# ExenMiniMotorShield.net
KiCad netlist of a schematic drawn in EAGLE
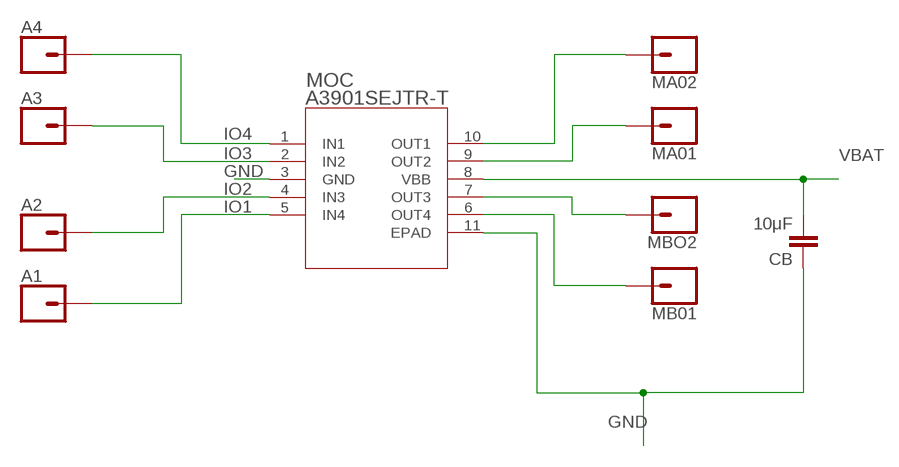
[diagram p0: schematic, sheet 1]
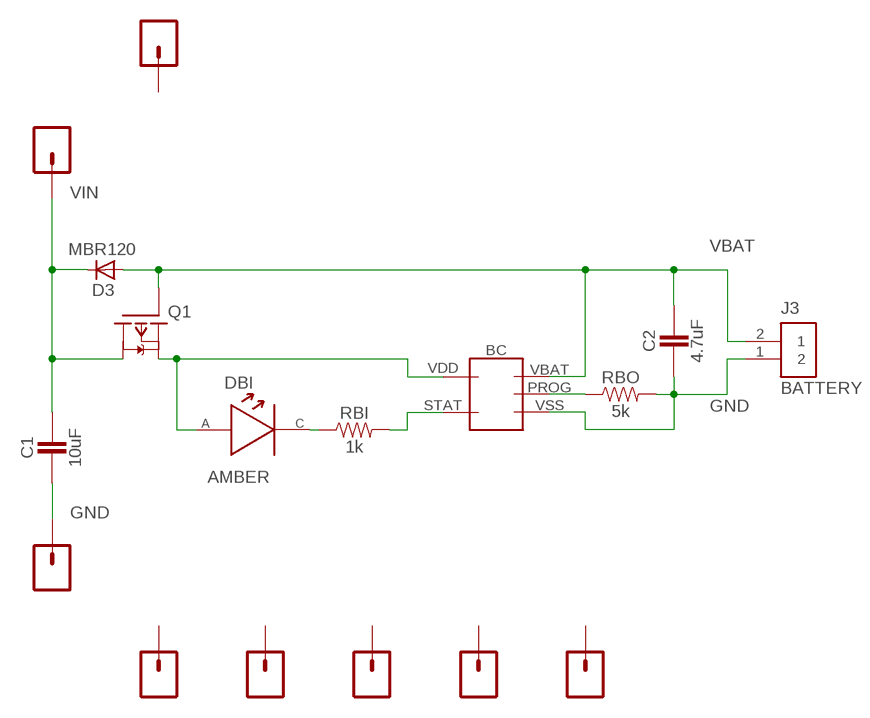
[diagram p1: schematic, sheet 2]

(export (version "E")
  (design (tool "Eeschema 10.0.6"))
  (components
    (comp (ref "A1")
      (value "CONN_01PTH_NO_SILK_YES_STOP")
      (footprint "eagle-import:1X01_NO_SILK")
      (libsource (lib "eagle-import") (part "CONN_01PTH_NO_SILK_YES_STOP"))
    )
    (comp (ref "A2")
      (value "CONN_01PTH_NO_SILK_YES_STOP")
      (footprint "eagle-import:1X01_NO_SILK")
      (libsource (lib "eagle-import") (part "CONN_01PTH_NO_SILK_YES_STOP"))
    )
    (comp (ref "A3")
      (value "CONN_01PTH_NO_SILK_YES_STOP")
      (footprint "eagle-import:1X01_NO_SILK")
      (libsource (lib "eagle-import") (part "CONN_01PTH_NO_SILK_YES_STOP"))
    )
    (comp (ref "A4")
      (value "CONN_01PTH_NO_SILK_YES_STOP")
      (footprint "eagle-import:1X01_NO_SILK")
      (libsource (lib "eagle-import") (part "CONN_01PTH_NO_SILK_YES_STOP"))
    )
    (comp (ref "CB")
      (value "10μF")
      (footprint "eagle-import:0603")
      (libsource (lib "eagle-import") (part "4.7PF-0603-50V-5%"))
    )
    (comp (ref "MA01")
      (value "CONN_01PTH_NO_SILK_YES_STOP")
      (footprint "eagle-import:1X01_NO_SILK")
      (libsource (lib "eagle-import") (part "CONN_01PTH_NO_SILK_YES_STOP"))
    )
    (comp (ref "MA02")
      (value "CONN_01PTH_NO_SILK_YES_STOP")
      (footprint "eagle-import:1X01_NO_SILK")
      (libsource (lib "eagle-import") (part "CONN_01PTH_NO_SILK_YES_STOP"))
    )
    (comp (ref "MB01")
      (value "CONN_01PTH_NO_SILK_YES_STOP")
      (footprint "eagle-import:1X01_NO_SILK")
      (libsource (lib "eagle-import") (part "CONN_01PTH_NO_SILK_YES_STOP"))
    )
    (comp (ref "MBO2")
      (value "CONN_01PTH_NO_SILK_YES_STOP")
      (footprint "eagle-import:1X01_NO_SILK")
      (libsource (lib "eagle-import") (part "CONN_01PTH_NO_SILK_YES_STOP"))
    )
    (comp (ref "MOC")
      (value "A3901SEJTR-T")
      (footprint "eagle-import:DFN-10_DD")
      (libsource (lib "eagle-import") (part "A3901SEJTR-T"))
    )
    (comp (ref "+3.3")
      (value "CONN_01PTH_NO_SILK_YES_STOP")
      (footprint "eagle-import:1X01_NO_SILK")
      (libsource (lib "eagle-import") (part "CONN_01PTH_NO_SILK_YES_STOP"))
    )
    (comp (ref "BC")
      (value "BATTERYCHARGER")
      (footprint "eagle-import:SOT-753")
      (libsource (lib "eagle-import") (part "BATTERYCHARGER"))
    )
    (comp (ref "C1")
      (value "10uF")
      (footprint "eagle-import:PASSIVE-0603")
      (libsource (lib "eagle-import") (part "CAPACITOR"))
    )
    (comp (ref "C2")
      (value "4.7uF")
      (footprint "eagle-import:PASSIVE-0603")
      (libsource (lib "eagle-import") (part "CAPACITOR"))
    )
    (comp (ref "D0")
      (value "CONN_01PTH_NO_SILK_YES_STOP")
      (footprint "eagle-import:1X01_NO_SILK")
      (libsource (lib "eagle-import") (part "CONN_01PTH_NO_SILK_YES_STOP"))
    )
    (comp (ref "D1")
      (value "CONN_01PTH_NO_SILK_YES_STOP")
      (footprint "eagle-import:1X01_NO_SILK")
      (libsource (lib "eagle-import") (part "CONN_01PTH_NO_SILK_YES_STOP"))
    )
    (comp (ref "D3")
      (value "MBR120")
      (footprint "eagle-import:SOD-123FL")
      (fields (field (name "PARTNO") "AS-ITM-00111"))
      (libsource (lib "eagle-import") (part "AS-ITM-00111"))
    )
    (comp (ref "DBI")
      (value "AMBER")
      (footprint "eagle-import:PASSIVE-0603")
      (libsource (lib "eagle-import") (part "DIODE"))
    )
    (comp (ref "GND")
      (value "CONN_01PTH_NO_SILK_YES_STOP")
      (footprint "eagle-import:1X01_NO_SILK")
      (libsource (lib "eagle-import") (part "CONN_01PTH_NO_SILK_YES_STOP"))
    )
    (comp (ref "J3")
      (value "BATTERY")
      (footprint "eagle-import:JST_SH_2X1")
      (fields (field (name "PARTNO") "AS-ITM-00231"))
      (libsource (lib "eagle-import") (part "AS-ITM-00231"))
    )
    (comp (ref "Q1")
      (value "DMP2035U")
      (footprint "eagle-import:SOT23")
      (fields (field (name "PARTNO") "AS-ITM-00024"))
      (libsource (lib "eagle-import") (part "AS-ITM-00024"))
    )
    (comp (ref "RBI")
      (value "1k")
      (footprint "eagle-import:PASSIVE-0603")
      (libsource (lib "eagle-import") (part "RESISTOR"))
    )
    (comp (ref "RBO")
      (value "5k")
      (footprint "eagle-import:PASSIVE-0603")
      (libsource (lib "eagle-import") (part "RESISTOR"))
    )
    (comp (ref "RST")
      (value "CONN_01PTH_NO_SILK_YES_STOP")
      (footprint "eagle-import:1X01_NO_SILK")
      (libsource (lib "eagle-import") (part "CONN_01PTH_NO_SILK_YES_STOP"))
    )
    (comp (ref "SCL")
      (value "CONN_01PTH_NO_SILK_YES_STOP")
      (footprint "eagle-import:1X01_NO_SILK")
      (libsource (lib "eagle-import") (part "CONN_01PTH_NO_SILK_YES_STOP"))
    )
    (comp (ref "SDA")
      (value "CONN_01PTH_NO_SILK_YES_STOP")
      (footprint "eagle-import:1X01_NO_SILK")
      (libsource (lib "eagle-import") (part "CONN_01PTH_NO_SILK_YES_STOP"))
    )
    (comp (ref "VIN")
      (value "CONN_01PTH_NO_SILK_YES_STOP")
      (footprint "eagle-import:1X01_NO_SILK")
      (libsource (lib "eagle-import") (part "CONN_01PTH_NO_SILK_YES_STOP"))
    )
  )
  (nets
    (net (code "1") (name "GND") (class "Default")
      (node (ref "BC") (pin "VSS") (pinfunction "VSS_VSS") (pintype "bidirectional"))
      (node (ref "C1") (pin "1") (pinfunction "1_1") (pintype "passive"))
      (node (ref "C2") (pin "1") (pinfunction "1_1") (pintype "passive"))
      (node (ref "CB") (pin "1") (pinfunction "1_1") (pintype "passive"))
      (node (ref "GND") (pin "1") (pinfunction "1_1") (pintype "passive"))
      (node (ref "J3") (pin "1") (pinfunction "2_1") (pintype "bidirectional"))
      (node (ref "MOC") (pin "11") (pinfunction "EPAD_11") (pintype "passive"))
      (node (ref "MOC") (pin "3") (pinfunction "GND_3") (pintype "power_in"))
      (node (ref "RBO") (pin "2") (pinfunction "2_2") (pintype "passive"))
    )
    (net (code "2") (name "IO1") (class "Default")
      (node (ref "A1") (pin "1") (pinfunction "1_1") (pintype "passive"))
      (node (ref "MOC") (pin "5") (pinfunction "IN4_5") (pintype "passive"))
    )
    (net (code "3") (name "IO2") (class "Default")
      (node (ref "A2") (pin "1") (pinfunction "1_1") (pintype "passive"))
      (node (ref "MOC") (pin "4") (pinfunction "IN3_4") (pintype "passive"))
    )
    (net (code "4") (name "IO3") (class "Default")
      (node (ref "A3") (pin "1") (pinfunction "1_1") (pintype "passive"))
      (node (ref "MOC") (pin "2") (pinfunction "IN2_2") (pintype "passive"))
    )
    (net (code "5") (name "IO4") (class "Default")
      (node (ref "A4") (pin "1") (pinfunction "1_1") (pintype "passive"))
      (node (ref "MOC") (pin "1") (pinfunction "IN1_1") (pintype "passive"))
    )
    (net (code "6") (name "Net-(BC-PadPROG)") (class "Default")
      (node (ref "BC") (pin "PROG") (pinfunction "PROG_PROG") (pintype "bidirectional"))
      (node (ref "RBO") (pin "1") (pinfunction "1_1") (pintype "passive"))
    )
    (net (code "7") (name "Net-(BC-PadSTAT)") (class "Default")
      (node (ref "BC") (pin "STAT") (pinfunction "STAT_STAT") (pintype "bidirectional"))
      (node (ref "RBI") (pin "2") (pinfunction "2_2") (pintype "passive"))
    )
    (net (code "8") (name "Net-(DBI-ANODE)") (class "Default")
      (node (ref "BC") (pin "VDD") (pinfunction "VDD_VDD") (pintype "bidirectional"))
      (node (ref "DBI") (pin "1") (pinfunction "ANODE_1") (pintype "bidirectional"))
      (node (ref "Q1") (pin "E") (pinfunction "S_E") (pintype "passive"))
    )
    (net (code "9") (name "Net-(DBI-CATHODE)") (class "Default")
      (node (ref "DBI") (pin "2") (pinfunction "CATHODE_2") (pintype "bidirectional"))
      (node (ref "RBI") (pin "1") (pinfunction "1_1") (pintype "passive"))
    )
    (net (code "10") (name "Net-(MOC-OUT1)") (class "Default")
      (node (ref "MA02") (pin "1") (pinfunction "1_1") (pintype "passive"))
      (node (ref "MOC") (pin "10") (pinfunction "OUT1_10") (pintype "output"))
    )
    (net (code "11") (name "Net-(MOC-OUT2)") (class "Default")
      (node (ref "MA01") (pin "1") (pinfunction "1_1") (pintype "passive"))
      (node (ref "MOC") (pin "9") (pinfunction "OUT2_9") (pintype "output"))
    )
    (net (code "12") (name "Net-(MOC-OUT3)") (class "Default")
      (node (ref "MBO2") (pin "1") (pinfunction "1_1") (pintype "passive"))
      (node (ref "MOC") (pin "7") (pinfunction "OUT3_7") (pintype "output"))
    )
    (net (code "13") (name "Net-(MOC-OUT4)") (class "Default")
      (node (ref "MB01") (pin "1") (pinfunction "1_1") (pintype "passive"))
      (node (ref "MOC") (pin "6") (pinfunction "OUT4_6") (pintype "output"))
    )
    (net (code "14") (name "VBAT") (class "Default")
      (node (ref "BC") (pin "VBAT") (pinfunction "VBAT_VBAT") (pintype "bidirectional"))
      (node (ref "C2") (pin "2") (pinfunction "2_2") (pintype "passive"))
      (node (ref "CB") (pin "2") (pinfunction "2_2") (pintype "passive"))
      (node (ref "D3") (pin "A") (pinfunction "A_A") (pintype "passive"))
      (node (ref "J3") (pin "2") (pinfunction "1_2") (pintype "bidirectional"))
      (node (ref "MOC") (pin "8") (pinfunction "VBB_8") (pintype "power_in"))
      (node (ref "Q1") (pin "B") (pinfunction "G_B") (pintype "passive"))
    )
    (net (code "15") (name "VIN") (class "Default")
      (node (ref "C1") (pin "2") (pinfunction "2_2") (pintype "passive"))
      (node (ref "D3") (pin "C") (pinfunction "C_C") (pintype "passive"))
      (node (ref "Q1") (pin "C") (pinfunction "D_C") (pintype "passive"))
      (node (ref "VIN") (pin "1") (pinfunction "1_1") (pintype "passive"))
    )
    (net (code "16") (name "unconnected-(+3.3-Pad1)") (class "Default")
      (node (ref "+3.3") (pin "1") (pinfunction "1_1") (pintype "passive"))
    )
    (net (code "17") (name "unconnected-(D0-Pad1)") (class "Default")
      (node (ref "D0") (pin "1") (pinfunction "1_1") (pintype "passive"))
    )
    (net (code "18") (name "unconnected-(D1-Pad1)") (class "Default")
      (node (ref "D1") (pin "1") (pinfunction "1_1") (pintype "passive"))
    )
    (net (code "19") (name "unconnected-(RST-Pad1)") (class "Default")
      (node (ref "RST") (pin "1") (pinfunction "1_1") (pintype "passive"))
    )
    (net (code "20") (name "unconnected-(SCL-Pad1)") (class "Default")
      (node (ref "SCL") (pin "1") (pinfunction "1_1") (pintype "passive"))
    )
    (net (code "21") (name "unconnected-(SDA-Pad1)") (class "Default")
      (node (ref "SDA") (pin "1") (pinfunction "1_1") (pintype "passive"))
    )
  )
)
